# transistor_logic.net
KiCad netlist of a schematic drawn in EAGLE
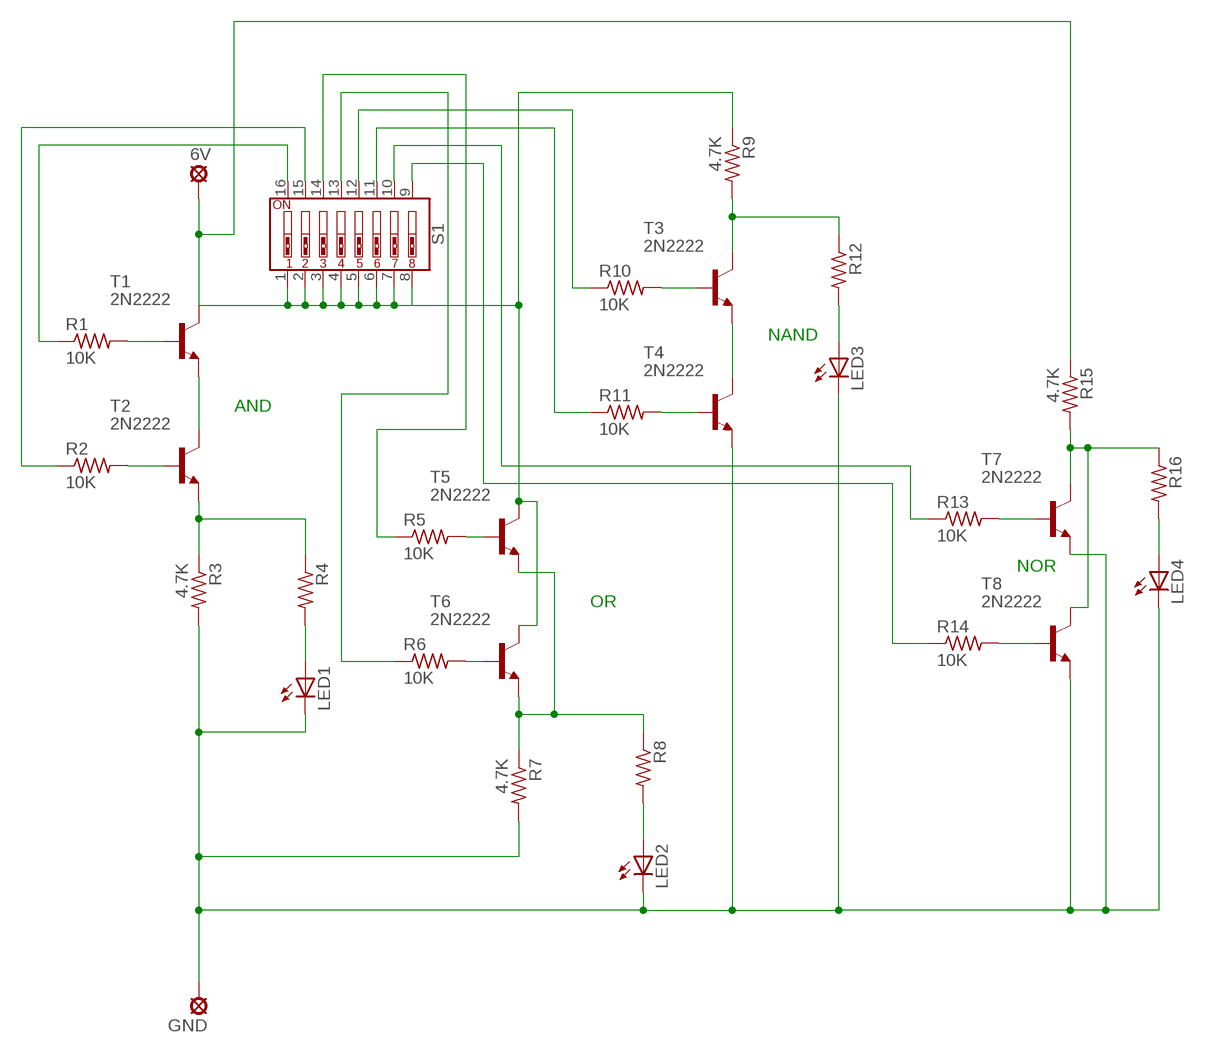
[diagram p0: schematic, sheet 1]

(export (version "E")
  (design (tool "Eeschema 10.0.6"))
  (components
    (comp (ref "6V")
      (value "6V")
      (footprint "eagle-import:LSP07")
      (libsource (lib "eagle-import") (part "LSP07"))
    )
    (comp (ref "GND")
      (value "GND")
      (footprint "eagle-import:LSP07")
      (libsource (lib "eagle-import") (part "LSP07"))
    )
    (comp (ref "LED1")
      (value "LED5MM")
      (footprint "eagle-import:LED5MM")
      (libsource (lib "eagle-import") (part "LED5MM"))
    )
    (comp (ref "LED2")
      (value "LED5MM")
      (footprint "eagle-import:LED5MM")
      (libsource (lib "eagle-import") (part "LED5MM"))
    )
    (comp (ref "LED3")
      (value "LED5MM")
      (footprint "eagle-import:LED5MM")
      (libsource (lib "eagle-import") (part "LED5MM"))
    )
    (comp (ref "LED4")
      (value "LED5MM")
      (footprint "eagle-import:LED5MM")
      (libsource (lib "eagle-import") (part "LED5MM"))
    )
    (comp (ref "R1")
      (value "10K")
      (footprint "eagle-import:0207_9")
      (libsource (lib "eagle-import") (part "R-US_0207/9"))
    )
    (comp (ref "R2")
      (value "10K")
      (footprint "eagle-import:0207_9")
      (libsource (lib "eagle-import") (part "R-US_0207/9"))
    )
    (comp (ref "R3")
      (value "4.7K")
      (footprint "eagle-import:0207_9")
      (libsource (lib "eagle-import") (part "R-US_0207/9"))
    )
    (comp (ref "R4")
      (value "R-US_0207/9")
      (footprint "eagle-import:0207_9")
      (libsource (lib "eagle-import") (part "R-US_0207/9"))
    )
    (comp (ref "R5")
      (value "10K")
      (footprint "eagle-import:0207_9")
      (libsource (lib "eagle-import") (part "R-US_0207/9"))
    )
    (comp (ref "R6")
      (value "10K")
      (footprint "eagle-import:0207_9")
      (libsource (lib "eagle-import") (part "R-US_0207/9"))
    )
    (comp (ref "R7")
      (value "4.7K")
      (footprint "eagle-import:0207_9")
      (libsource (lib "eagle-import") (part "R-US_0207/9"))
    )
    (comp (ref "R8")
      (value "R-US_0207/9")
      (footprint "eagle-import:0207_9")
      (libsource (lib "eagle-import") (part "R-US_0207/9"))
    )
    (comp (ref "R9")
      (value "4.7K")
      (footprint "eagle-import:0207_9")
      (libsource (lib "eagle-import") (part "R-US_0207/9"))
    )
    (comp (ref "R10")
      (value "10K")
      (footprint "eagle-import:0207_9")
      (libsource (lib "eagle-import") (part "R-US_0207/9"))
    )
    (comp (ref "R11")
      (value "10K")
      (footprint "eagle-import:0207_9")
      (libsource (lib "eagle-import") (part "R-US_0207/9"))
    )
    (comp (ref "R12")
      (value "R-US_0207/9")
      (footprint "eagle-import:0207_9")
      (libsource (lib "eagle-import") (part "R-US_0207/9"))
    )
    (comp (ref "R13")
      (value "10K")
      (footprint "eagle-import:0207_9")
      (libsource (lib "eagle-import") (part "R-US_0207/9"))
    )
    (comp (ref "R14")
      (value "10K")
      (footprint "eagle-import:0207_9")
      (libsource (lib "eagle-import") (part "R-US_0207/9"))
    )
    (comp (ref "R15")
      (value "4.7K")
      (footprint "eagle-import:0207_9")
      (libsource (lib "eagle-import") (part "R-US_0207/9"))
    )
    (comp (ref "R16")
      (value "R-US_0207/9")
      (footprint "eagle-import:0207_9")
      (libsource (lib "eagle-import") (part "R-US_0207/9"))
    )
    (comp (ref "S1")
      (value "DIP-08-PTH")
      (footprint "eagle-import:DIPSWITCH-08")
      (libsource (lib "eagle-import") (part "DIP-08-PTH"))
    )
    (comp (ref "T1")
      (value "2N2222")
      (footprint "eagle-import:TO92-EBC-OVAL")
      (libsource (lib "eagle-import") (part "2N2222"))
    )
    (comp (ref "T2")
      (value "2N2222")
      (footprint "eagle-import:TO92-EBC-OVAL")
      (libsource (lib "eagle-import") (part "2N2222"))
    )
    (comp (ref "T3")
      (value "2N2222")
      (footprint "eagle-import:TO92-EBC-OVAL")
      (libsource (lib "eagle-import") (part "2N2222"))
    )
    (comp (ref "T4")
      (value "2N2222")
      (footprint "eagle-import:TO92-EBC-OVAL")
      (libsource (lib "eagle-import") (part "2N2222"))
    )
    (comp (ref "T5")
      (value "2N2222")
      (footprint "eagle-import:TO92-EBC-OVAL")
      (libsource (lib "eagle-import") (part "2N2222"))
    )
    (comp (ref "T6")
      (value "2N2222")
      (footprint "eagle-import:TO92-EBC-OVAL")
      (libsource (lib "eagle-import") (part "2N2222"))
    )
    (comp (ref "T7")
      (value "2N2222")
      (footprint "eagle-import:TO92-EBC-OVAL")
      (libsource (lib "eagle-import") (part "2N2222"))
    )
    (comp (ref "T8")
      (value "2N2222")
      (footprint "eagle-import:TO92-EBC-OVAL")
      (libsource (lib "eagle-import") (part "2N2222"))
    )
  )
  (nets
    (net (code "1") (name "Net-(6V-MP)") (class "Default")
      (node (ref "6V") (pin "P$1") (pinfunction "MP_P$1") (pintype "passive"))
      (node (ref "R15") (pin "1") (pinfunction "1_1") (pintype "passive"))
      (node (ref "R9") (pin "1") (pinfunction "1_1") (pintype "passive"))
      (node (ref "S1") (pin "1") (pinfunction "1_1") (pintype "passive"))
      (node (ref "S1") (pin "2") (pinfunction "2_2") (pintype "passive"))
      (node (ref "S1") (pin "3") (pinfunction "3_3") (pintype "passive"))
      (node (ref "S1") (pin "4") (pinfunction "4_4") (pintype "passive"))
      (node (ref "S1") (pin "5") (pinfunction "5_5") (pintype "passive"))
      (node (ref "S1") (pin "6") (pinfunction "6_6") (pintype "passive"))
      (node (ref "S1") (pin "7") (pinfunction "7_7") (pintype "passive"))
      (node (ref "S1") (pin "8") (pinfunction "8_8") (pintype "passive"))
      (node (ref "T1") (pin "C") (pinfunction "C_C") (pintype "passive"))
      (node (ref "T5") (pin "C") (pinfunction "C_C") (pintype "passive"))
      (node (ref "T6") (pin "C") (pinfunction "C_C") (pintype "passive"))
    )
    (net (code "2") (name "Net-(GND-MP)") (class "Default")
      (node (ref "GND") (pin "P$1") (pinfunction "MP_P$1") (pintype "passive"))
      (node (ref "LED1") (pin "K") (pinfunction "C_K") (pintype "passive"))
      (node (ref "LED2") (pin "K") (pinfunction "C_K") (pintype "passive"))
      (node (ref "LED3") (pin "K") (pinfunction "C_K") (pintype "passive"))
      (node (ref "LED4") (pin "K") (pinfunction "C_K") (pintype "passive"))
      (node (ref "R3") (pin "2") (pinfunction "2_2") (pintype "passive"))
      (node (ref "R7") (pin "2") (pinfunction "2_2") (pintype "passive"))
      (node (ref "T4") (pin "E") (pinfunction "E_E") (pintype "passive"))
      (node (ref "T7") (pin "E") (pinfunction "E_E") (pintype "passive"))
      (node (ref "T8") (pin "E") (pinfunction "E_E") (pintype "passive"))
    )
    (net (code "3") (name "Net-(LED1-PadA)") (class "Default")
      (node (ref "LED1") (pin "A") (pinfunction "A_A") (pintype "passive"))
      (node (ref "R4") (pin "2") (pinfunction "2_2") (pintype "passive"))
    )
    (net (code "4") (name "Net-(LED2-PadA)") (class "Default")
      (node (ref "LED2") (pin "A") (pinfunction "A_A") (pintype "passive"))
      (node (ref "R8") (pin "2") (pinfunction "2_2") (pintype "passive"))
    )
    (net (code "5") (name "Net-(LED3-PadA)") (class "Default")
      (node (ref "LED3") (pin "A") (pinfunction "A_A") (pintype "passive"))
      (node (ref "R12") (pin "2") (pinfunction "2_2") (pintype "passive"))
    )
    (net (code "6") (name "Net-(LED4-PadA)") (class "Default")
      (node (ref "LED4") (pin "A") (pinfunction "A_A") (pintype "passive"))
      (node (ref "R16") (pin "2") (pinfunction "2_2") (pintype "passive"))
    )
    (net (code "7") (name "Net-(R1-Pad1)") (class "Default")
      (node (ref "R1") (pin "1") (pinfunction "1_1") (pintype "passive"))
      (node (ref "S1") (pin "16") (pinfunction "16_16") (pintype "passive"))
    )
    (net (code "8") (name "Net-(R1-Pad2)") (class "Default")
      (node (ref "R1") (pin "2") (pinfunction "2_2") (pintype "passive"))
      (node (ref "T1") (pin "B") (pinfunction "B_B") (pintype "passive"))
    )
    (net (code "9") (name "Net-(R2-Pad1)") (class "Default")
      (node (ref "R2") (pin "1") (pinfunction "1_1") (pintype "passive"))
      (node (ref "S1") (pin "15") (pinfunction "15_15") (pintype "passive"))
    )
    (net (code "10") (name "Net-(R2-Pad2)") (class "Default")
      (node (ref "R2") (pin "2") (pinfunction "2_2") (pintype "passive"))
      (node (ref "T2") (pin "B") (pinfunction "B_B") (pintype "passive"))
    )
    (net (code "11") (name "Net-(R3-Pad1)") (class "Default")
      (node (ref "R3") (pin "1") (pinfunction "1_1") (pintype "passive"))
      (node (ref "R4") (pin "1") (pinfunction "1_1") (pintype "passive"))
      (node (ref "T2") (pin "E") (pinfunction "E_E") (pintype "passive"))
    )
    (net (code "12") (name "Net-(R5-Pad1)") (class "Default")
      (node (ref "R5") (pin "1") (pinfunction "1_1") (pintype "passive"))
      (node (ref "S1") (pin "14") (pinfunction "14_14") (pintype "passive"))
    )
    (net (code "13") (name "Net-(R5-Pad2)") (class "Default")
      (node (ref "R5") (pin "2") (pinfunction "2_2") (pintype "passive"))
      (node (ref "T5") (pin "B") (pinfunction "B_B") (pintype "passive"))
    )
    (net (code "14") (name "Net-(R6-Pad1)") (class "Default")
      (node (ref "R6") (pin "1") (pinfunction "1_1") (pintype "passive"))
      (node (ref "S1") (pin "13") (pinfunction "13_13") (pintype "passive"))
    )
    (net (code "15") (name "Net-(R6-Pad2)") (class "Default")
      (node (ref "R6") (pin "2") (pinfunction "2_2") (pintype "passive"))
      (node (ref "T6") (pin "B") (pinfunction "B_B") (pintype "passive"))
    )
    (net (code "16") (name "Net-(R7-Pad1)") (class "Default")
      (node (ref "R7") (pin "1") (pinfunction "1_1") (pintype "passive"))
      (node (ref "R8") (pin "1") (pinfunction "1_1") (pintype "passive"))
      (node (ref "T5") (pin "E") (pinfunction "E_E") (pintype "passive"))
      (node (ref "T6") (pin "E") (pinfunction "E_E") (pintype "passive"))
    )
    (net (code "17") (name "Net-(R10-Pad1)") (class "Default")
      (node (ref "R10") (pin "1") (pinfunction "1_1") (pintype "passive"))
      (node (ref "S1") (pin "12") (pinfunction "12_12") (pintype "passive"))
    )
    (net (code "18") (name "Net-(R10-Pad2)") (class "Default")
      (node (ref "R10") (pin "2") (pinfunction "2_2") (pintype "passive"))
      (node (ref "T3") (pin "B") (pinfunction "B_B") (pintype "passive"))
    )
    (net (code "19") (name "Net-(R11-Pad1)") (class "Default")
      (node (ref "R11") (pin "1") (pinfunction "1_1") (pintype "passive"))
      (node (ref "S1") (pin "11") (pinfunction "11_11") (pintype "passive"))
    )
    (net (code "20") (name "Net-(R11-Pad2)") (class "Default")
      (node (ref "R11") (pin "2") (pinfunction "2_2") (pintype "passive"))
      (node (ref "T4") (pin "B") (pinfunction "B_B") (pintype "passive"))
    )
    (net (code "21") (name "Net-(R12-Pad1)") (class "Default")
      (node (ref "R12") (pin "1") (pinfunction "1_1") (pintype "passive"))
      (node (ref "R9") (pin "2") (pinfunction "2_2") (pintype "passive"))
      (node (ref "T3") (pin "C") (pinfunction "C_C") (pintype "passive"))
    )
    (net (code "22") (name "Net-(R13-Pad1)") (class "Default")
      (node (ref "R13") (pin "1") (pinfunction "1_1") (pintype "passive"))
      (node (ref "S1") (pin "10") (pinfunction "10_10") (pintype "passive"))
    )
    (net (code "23") (name "Net-(R13-Pad2)") (class "Default")
      (node (ref "R13") (pin "2") (pinfunction "2_2") (pintype "passive"))
      (node (ref "T7") (pin "B") (pinfunction "B_B") (pintype "passive"))
    )
    (net (code "24") (name "Net-(R14-Pad1)") (class "Default")
      (node (ref "R14") (pin "1") (pinfunction "1_1") (pintype "passive"))
      (node (ref "S1") (pin "9") (pinfunction "9_9") (pintype "passive"))
    )
    (net (code "25") (name "Net-(R14-Pad2)") (class "Default")
      (node (ref "R14") (pin "2") (pinfunction "2_2") (pintype "passive"))
      (node (ref "T8") (pin "B") (pinfunction "B_B") (pintype "passive"))
    )
    (net (code "26") (name "Net-(R15-Pad2)") (class "Default")
      (node (ref "R15") (pin "2") (pinfunction "2_2") (pintype "passive"))
      (node (ref "R16") (pin "1") (pinfunction "1_1") (pintype "passive"))
      (node (ref "T7") (pin "C") (pinfunction "C_C") (pintype "passive"))
      (node (ref "T8") (pin "C") (pinfunction "C_C") (pintype "passive"))
    )
    (net (code "27") (name "Net-(T1-PadE)") (class "Default")
      (node (ref "T1") (pin "E") (pinfunction "E_E") (pintype "passive"))
      (node (ref "T2") (pin "C") (pinfunction "C_C") (pintype "passive"))
    )
    (net (code "28") (name "Net-(T3-PadE)") (class "Default")
      (node (ref "T3") (pin "E") (pinfunction "E_E") (pintype "passive"))
      (node (ref "T4") (pin "C") (pinfunction "C_C") (pintype "passive"))
    )
  )
)
